# Antenna_Board_v2.net
KiCad netlist of a schematic drawn in EAGLE
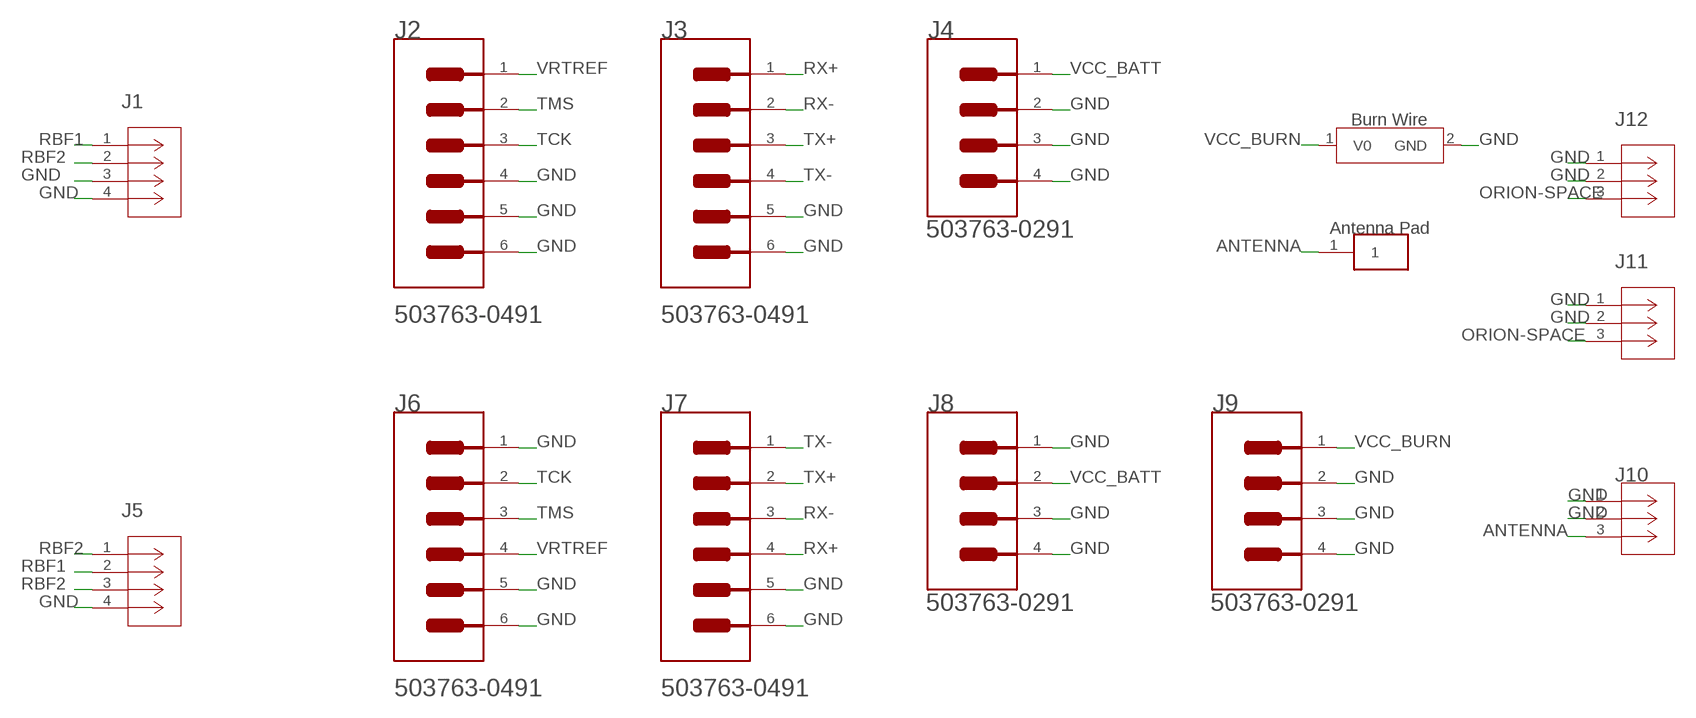
[diagram p0: schematic, sheet 1]

(export (version "E")
  (design (tool "Eeschema 10.0.6"))
  (components
    (comp (ref "J1")
      (value "5037630291")
      (footprint "eagle-import:CON_5037630291")
      (fields (field (name "COPYRIGHT") "Copyright (C) 2018 Accelerated Designs. All rights reserved"))
      (libsource (lib "eagle-import") (part "5037630291"))
    )
    (comp (ref "J2")
      (value "MOLEX_503763-0491MOLEX_503763-0491_0_0")
      (footprint "eagle-import:MOLEX_503763-0491_0")
      (fields
        (field (name "DIGIKEY_PART_NUMBER") "WM10655CT-ND")
        (field (name "MF") "Molex")
        (field (name "MOUSER_PART_NUMBER") "538-503763-0491")
      )
      (libsource (lib "eagle-import") (part "MOLEX_503763-0491MOLEX_503763-0491_0_0"))
    )
    (comp (ref "J3")
      (value "MOLEX_503763-0491MOLEX_503763-0491_0_0")
      (footprint "eagle-import:MOLEX_503763-0491_0")
      (fields
        (field (name "DIGIKEY_PART_NUMBER") "WM10655CT-ND")
        (field (name "MF") "Molex")
        (field (name "MOUSER_PART_NUMBER") "538-503763-0491")
      )
      (libsource (lib "eagle-import") (part "MOLEX_503763-0491MOLEX_503763-0491_0_0"))
    )
    (comp (ref "J4")
      (value "MOLEX_503763-0291MOLEX_503763-0291_0_0")
      (footprint "eagle-import:MOLEX_503763-0291_0")
      (fields
        (field (name "DIGIKEY_PART_NUMBER") "WM10654CT-ND")
        (field (name "MF") "Molex")
        (field (name "MOUSER_PART_NUMBER") "538-503763-0291")
      )
      (libsource (lib "eagle-import") (part "MOLEX_503763-0291MOLEX_503763-0291_0_0"))
    )
    (comp (ref "J5")
      (value "5037630291")
      (footprint "eagle-import:CON_5037630291")
      (fields (field (name "COPYRIGHT") "Copyright (C) 2018 Accelerated Designs. All rights reserved"))
      (libsource (lib "eagle-import") (part "5037630291"))
    )
    (comp (ref "J6")
      (value "MOLEX_503763-0491MOLEX_503763-0491_0_0")
      (footprint "eagle-import:MOLEX_503763-0491_0")
      (fields
        (field (name "DIGIKEY_PART_NUMBER") "WM10655CT-ND")
        (field (name "MF") "Molex")
        (field (name "MOUSER_PART_NUMBER") "538-503763-0491")
      )
      (libsource (lib "eagle-import") (part "MOLEX_503763-0491MOLEX_503763-0491_0_0"))
    )
    (comp (ref "J7")
      (value "MOLEX_503763-0491MOLEX_503763-0491_0_0")
      (footprint "eagle-import:MOLEX_503763-0491_0")
      (fields
        (field (name "DIGIKEY_PART_NUMBER") "WM10655CT-ND")
        (field (name "MF") "Molex")
        (field (name "MOUSER_PART_NUMBER") "538-503763-0491")
      )
      (libsource (lib "eagle-import") (part "MOLEX_503763-0491MOLEX_503763-0491_0_0"))
    )
    (comp (ref "J8")
      (value "MOLEX_503763-0291MOLEX_503763-0291_0_0")
      (footprint "eagle-import:MOLEX_503763-0291_0")
      (fields
        (field (name "DIGIKEY_PART_NUMBER") "WM10654CT-ND")
        (field (name "MF") "Molex")
        (field (name "MOUSER_PART_NUMBER") "538-503763-0291")
      )
      (libsource (lib "eagle-import") (part "MOLEX_503763-0291MOLEX_503763-0291_0_0"))
    )
    (comp (ref "J9")
      (value "MOLEX_503763-0291MOLEX_503763-0291_0_0")
      (footprint "eagle-import:MOLEX_503763-0291_0")
      (fields
        (field (name "DIGIKEY_PART_NUMBER") "WM10654CT-ND")
        (field (name "MF") "Molex")
        (field (name "MOUSER_PART_NUMBER") "538-503763-0291")
      )
      (libsource (lib "eagle-import") (part "MOLEX_503763-0291MOLEX_503763-0291_0_0"))
    )
    (comp (ref "J10")
      (value "U.FL-R-SMT-1(01)")
      (footprint "eagle-import:CONN_-SMT-1(01)")
      (fields (field (name "COPYRIGHT") "Copyright (C) 2018 Accelerated Designs. All rights reserved"))
      (libsource (lib "eagle-import") (part "U.FL-R-SMT-1(01)_U.FL-R-SMT-1(01)"))
    )
    (comp (ref "J11")
      (value "U.FL-R-SMT-1(01)")
      (footprint "eagle-import:CONN_-SMT-1(01)")
      (fields (field (name "COPYRIGHT") "Copyright (C) 2018 Accelerated Designs. All rights reserved"))
      (libsource (lib "eagle-import") (part "U.FL-R-SMT-1(01)"))
    )
    (comp (ref "J12")
      (value "U.FL-R-SMT-1(01)")
      (footprint "eagle-import:CONN_-SMT-1(01)")
      (fields (field (name "COPYRIGHT") "Copyright (C) 2018 Accelerated Designs. All rights reserved"))
      (libsource (lib "eagle-import") (part "U.FL-R-SMT-1(01)"))
    )
    (comp (ref "U$2")
      (value "ANTENNA_PAD")
      (footprint "eagle-import:ANTENNA_PAD")
      (libsource (lib "eagle-import") (part "ANTENNA_PAD"))
    )
    (comp (ref "U$3")
      (value "BURNWIRE")
      (footprint "eagle-import:BURNWIRE")
      (libsource (lib "eagle-import") (part "BURNWIRE"))
    )
  )
  (nets
    (net (code "1") (name "/ANTENNA") (class "Default")
      (node (ref "J10") (pin "3") (pinfunction "3_3") (pintype "passive"))
      (node (ref "U$2") (pin "1") (pinfunction "1_1") (pintype "bidirectional"))
    )
    (net (code "2") (name "/GND") (class "Default")
      (node (ref "J1") (pin "3") (pinfunction "3_3") (pintype "passive"))
      (node (ref "J1") (pin "4") (pinfunction "4_4") (pintype "passive"))
      (node (ref "J10") (pin "1") (pinfunction "1_1") (pintype "passive"))
      (node (ref "J10") (pin "2") (pinfunction "2_2") (pintype "passive"))
      (node (ref "J11") (pin "1") (pinfunction "1_1") (pintype "passive"))
      (node (ref "J11") (pin "2") (pinfunction "2_2") (pintype "passive"))
      (node (ref "J12") (pin "1") (pinfunction "1_1") (pintype "passive"))
      (node (ref "J12") (pin "2") (pinfunction "2_2") (pintype "passive"))
      (node (ref "J2") (pin "4") (pinfunction "4_4") (pintype "passive"))
      (node (ref "J2") (pin "5") (pinfunction "MNT_1_5") (pintype "passive"))
      (node (ref "J2") (pin "6") (pinfunction "MNT_2_6") (pintype "passive"))
      (node (ref "J3") (pin "5") (pinfunction "MNT_1_5") (pintype "passive"))
      (node (ref "J3") (pin "6") (pinfunction "MNT_2_6") (pintype "passive"))
      (node (ref "J4") (pin "2") (pinfunction "2_2") (pintype "bidirectional"))
      (node (ref "J4") (pin "3") (pinfunction "MNT_1_3") (pintype "bidirectional"))
      (node (ref "J4") (pin "4") (pinfunction "MNT_2_4") (pintype "bidirectional"))
      (node (ref "J5") (pin "4") (pinfunction "4_4") (pintype "passive"))
      (node (ref "J6") (pin "1") (pinfunction "1_1") (pintype "passive"))
      (node (ref "J6") (pin "5") (pinfunction "MNT_1_5") (pintype "passive"))
      (node (ref "J6") (pin "6") (pinfunction "MNT_2_6") (pintype "passive"))
      (node (ref "J7") (pin "5") (pinfunction "MNT_1_5") (pintype "passive"))
      (node (ref "J7") (pin "6") (pinfunction "MNT_2_6") (pintype "passive"))
      (node (ref "J8") (pin "1") (pinfunction "1_1") (pintype "bidirectional"))
      (node (ref "J8") (pin "3") (pinfunction "MNT_1_3") (pintype "bidirectional"))
      (node (ref "J8") (pin "4") (pinfunction "MNT_2_4") (pintype "bidirectional"))
      (node (ref "J9") (pin "2") (pinfunction "2_2") (pintype "bidirectional"))
      (node (ref "J9") (pin "3") (pinfunction "MNT_1_3") (pintype "bidirectional"))
      (node (ref "J9") (pin "4") (pinfunction "MNT_2_4") (pintype "bidirectional"))
      (node (ref "U$3") (pin "2") (pinfunction "GND_2") (pintype "bidirectional"))
    )
    (net (code "3") (name "/ORION-SPACE") (class "Default")
      (node (ref "J11") (pin "3") (pinfunction "3_3") (pintype "passive"))
      (node (ref "J12") (pin "3") (pinfunction "3_3") (pintype "passive"))
    )
    (net (code "4") (name "/RBF1") (class "Default")
      (node (ref "J1") (pin "1") (pinfunction "1_1") (pintype "passive"))
      (node (ref "J5") (pin "2") (pinfunction "2_2") (pintype "passive"))
    )
    (net (code "5") (name "/RBF2") (class "Default")
      (node (ref "J1") (pin "2") (pinfunction "2_2") (pintype "passive"))
      (node (ref "J5") (pin "1") (pinfunction "1_1") (pintype "passive"))
      (node (ref "J5") (pin "3") (pinfunction "3_3") (pintype "passive"))
    )
    (net (code "6") (name "/RX+") (class "Default")
      (node (ref "J3") (pin "1") (pinfunction "1_1") (pintype "passive"))
      (node (ref "J7") (pin "4") (pinfunction "4_4") (pintype "passive"))
    )
    (net (code "7") (name "/RX-") (class "Default")
      (node (ref "J3") (pin "2") (pinfunction "2_2") (pintype "passive"))
      (node (ref "J7") (pin "3") (pinfunction "3_3") (pintype "passive"))
    )
    (net (code "8") (name "/TCK") (class "Default")
      (node (ref "J2") (pin "3") (pinfunction "3_3") (pintype "passive"))
      (node (ref "J6") (pin "2") (pinfunction "2_2") (pintype "passive"))
    )
    (net (code "9") (name "/TMS") (class "Default")
      (node (ref "J2") (pin "2") (pinfunction "2_2") (pintype "passive"))
      (node (ref "J6") (pin "3") (pinfunction "3_3") (pintype "passive"))
    )
    (net (code "10") (name "/TX+") (class "Default")
      (node (ref "J3") (pin "3") (pinfunction "3_3") (pintype "passive"))
      (node (ref "J7") (pin "2") (pinfunction "2_2") (pintype "passive"))
    )
    (net (code "11") (name "/TX-") (class "Default")
      (node (ref "J3") (pin "4") (pinfunction "4_4") (pintype "passive"))
      (node (ref "J7") (pin "1") (pinfunction "1_1") (pintype "passive"))
    )
    (net (code "12") (name "/VCC_BATT") (class "Default")
      (node (ref "J4") (pin "1") (pinfunction "1_1") (pintype "bidirectional"))
      (node (ref "J8") (pin "2") (pinfunction "2_2") (pintype "bidirectional"))
    )
    (net (code "13") (name "/VCC_BURN") (class "Default")
      (node (ref "J9") (pin "1") (pinfunction "1_1") (pintype "bidirectional"))
      (node (ref "U$3") (pin "1") (pinfunction "V0_1") (pintype "bidirectional"))
    )
    (net (code "14") (name "/VRTREF") (class "Default")
      (node (ref "J2") (pin "1") (pinfunction "1_1") (pintype "passive"))
      (node (ref "J6") (pin "4") (pinfunction "4_4") (pintype "passive"))
    )
  )
)
